# MCU.net
KiCad netlist of a schematic drawn in Altium Designer
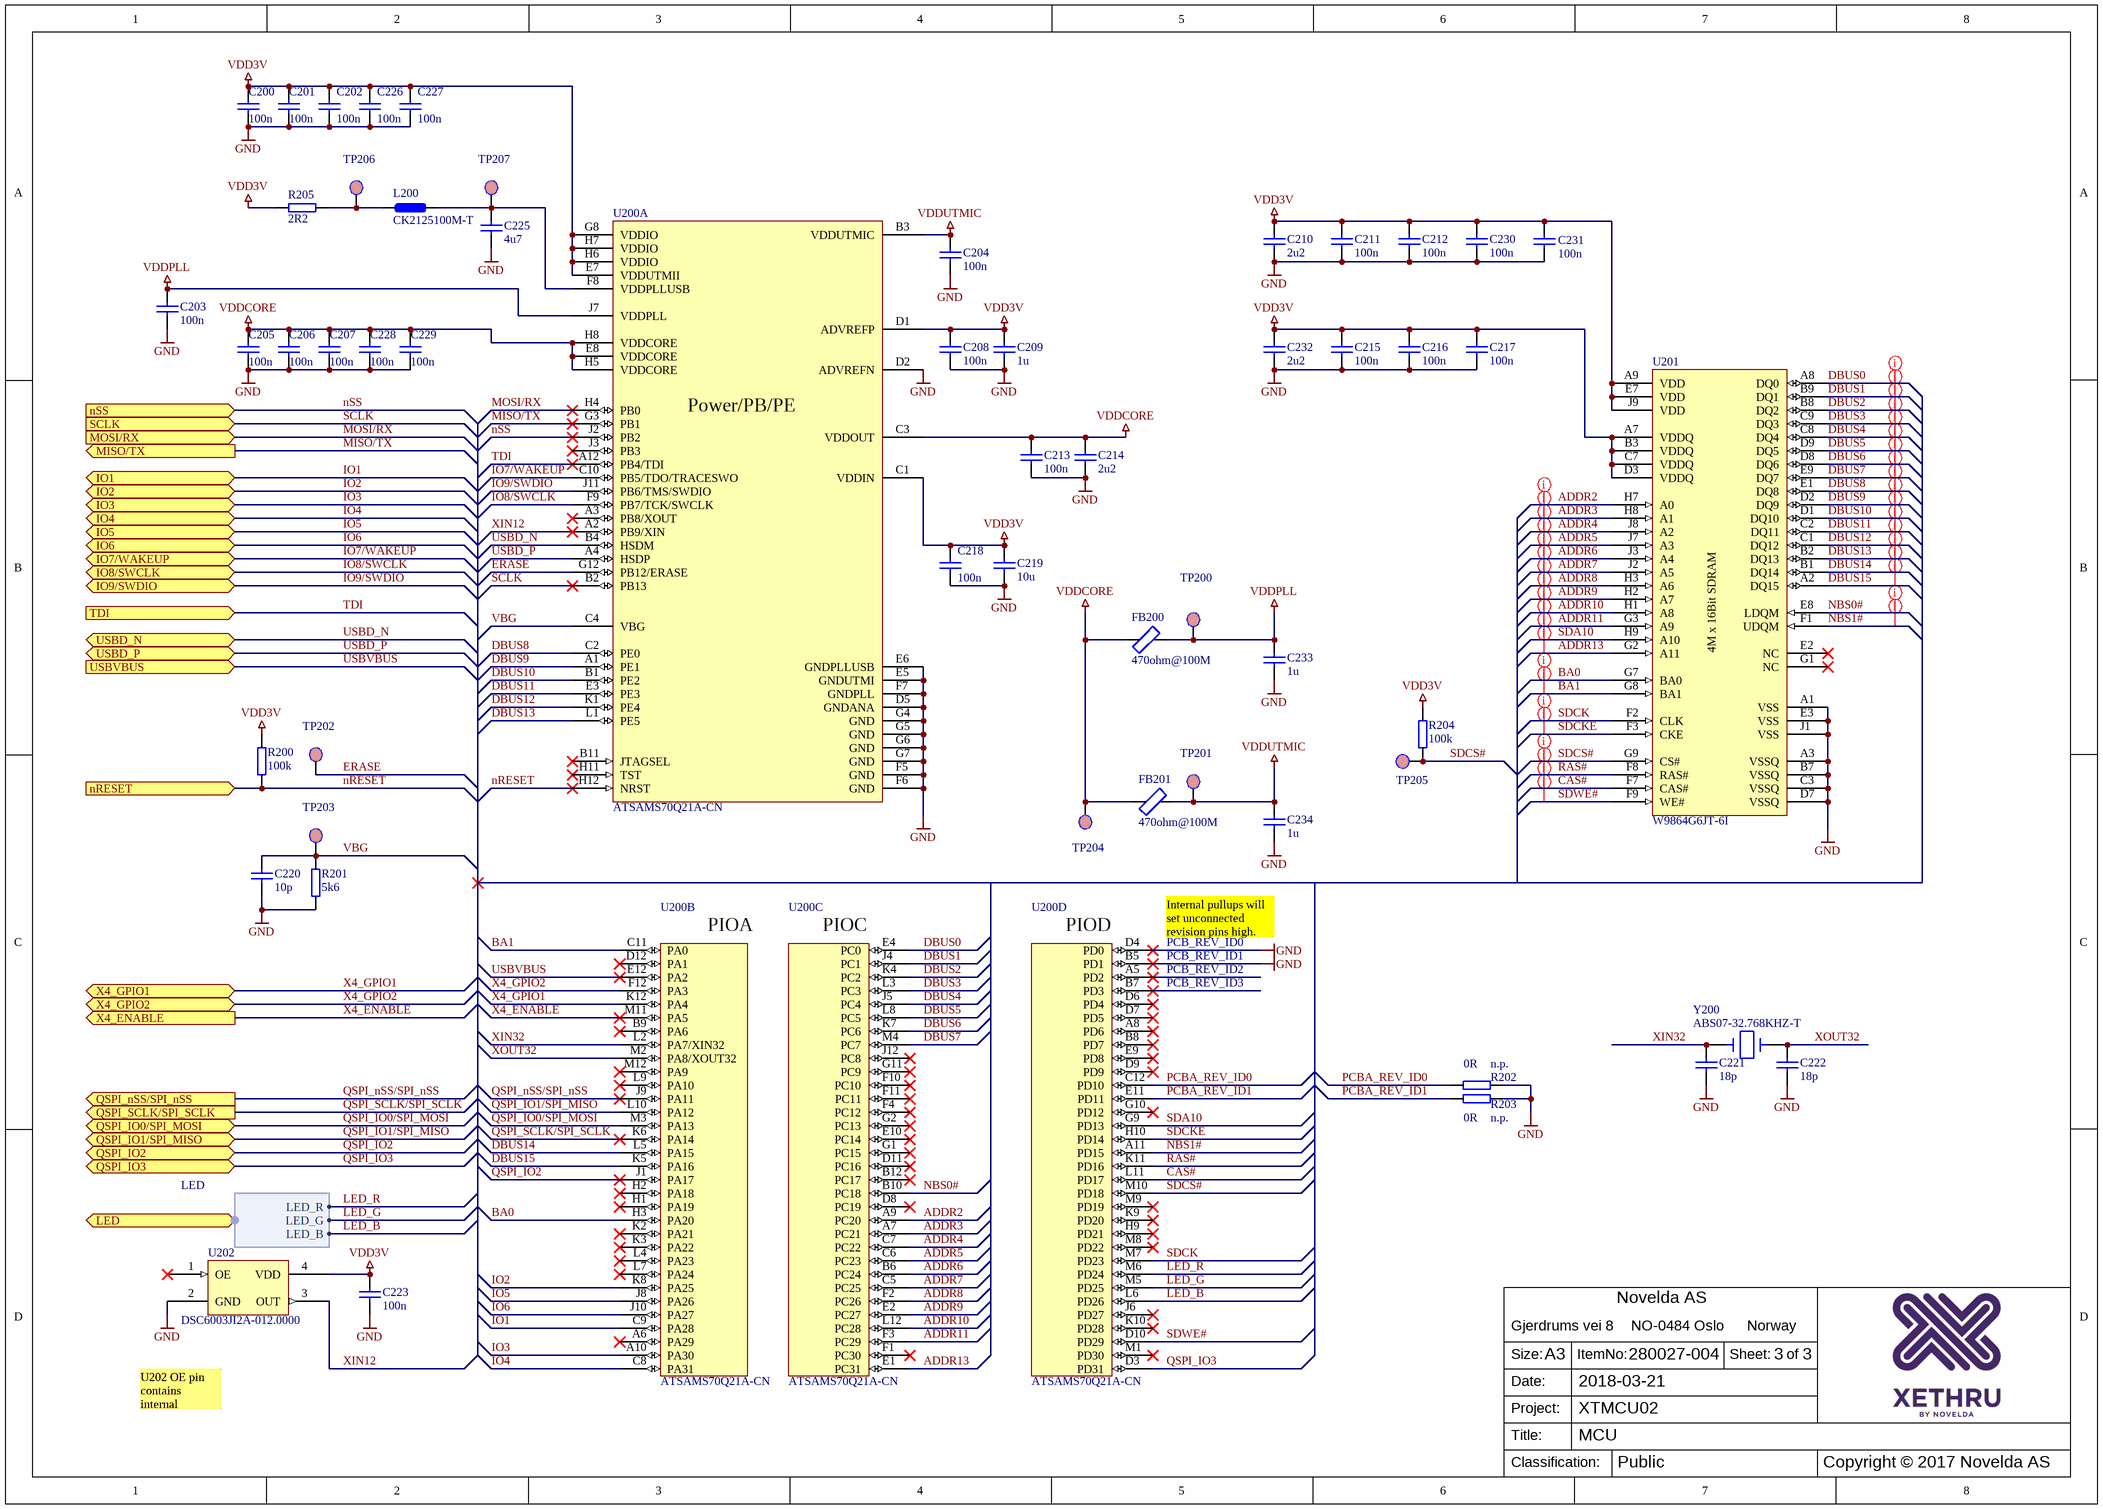
[diagram p0: MCU.SchDoc]

(export (version "E")
  (design (tool "Eeschema 10.0.6"))
  (components
    (comp (ref "C200")
      (value "100n")
      (footprint "0402-CAPACITOR-NONPOL")
      (description "CAPACITOR, 100n, 0402, 10%, 10V, X5R")
      (fields (field (name "MANUFACTURER") "--"))
      (libsource (lib "novelda_altiumlib") (part "CAPACITOR-NONPOL"))
    )
    (comp (ref "C201")
      (value "100n")
      (footprint "0402-CAPACITOR-NONPOL")
      (description "CAPACITOR, 100n, 0402, 10%, 10V, X5R")
      (fields (field (name "MANUFACTURER") "--"))
      (libsource (lib "novelda_altiumlib") (part "CAPACITOR-NONPOL"))
    )
    (comp (ref "C202")
      (value "100n")
      (footprint "0402-CAPACITOR-NONPOL")
      (description "CAPACITOR, 100n, 0402, 10%, 10V, X5R")
      (fields (field (name "MANUFACTURER") "--"))
      (libsource (lib "novelda_altiumlib") (part "CAPACITOR-NONPOL"))
    )
    (comp (ref "C203")
      (value "100n")
      (footprint "0402-CAPACITOR-NONPOL")
      (description "CAPACITOR, 100n, 0402, 10%, 10V, X5R")
      (fields (field (name "MANUFACTURER") "--"))
      (libsource (lib "novelda_altiumlib") (part "CAPACITOR-NONPOL"))
    )
    (comp (ref "C204")
      (value "100n")
      (footprint "0402-CAPACITOR-NONPOL")
      (description "CAPACITOR, 100n, 0402, 10%, 10V, X5R")
      (fields (field (name "MANUFACTURER") "--"))
      (libsource (lib "novelda_altiumlib") (part "CAPACITOR-NONPOL"))
    )
    (comp (ref "C205")
      (value "100n")
      (footprint "0402-CAPACITOR-NONPOL")
      (description "CAPACITOR, 100n, 0402, 10%, 10V, X5R")
      (fields (field (name "MANUFACTURER") "--"))
      (libsource (lib "novelda_altiumlib") (part "CAPACITOR-NONPOL"))
    )
    (comp (ref "C206")
      (value "100n")
      (footprint "0402-CAPACITOR-NONPOL")
      (description "CAPACITOR, 100n, 0402, 10%, 10V, X5R")
      (fields (field (name "MANUFACTURER") "--"))
      (libsource (lib "novelda_altiumlib") (part "CAPACITOR-NONPOL"))
    )
    (comp (ref "C207")
      (value "100n")
      (footprint "0402-CAPACITOR-NONPOL")
      (description "CAPACITOR, 100n, 0402, 10%, 10V, X5R")
      (fields (field (name "MANUFACTURER") "--"))
      (libsource (lib "novelda_altiumlib") (part "CAPACITOR-NONPOL"))
    )
    (comp (ref "C208")
      (value "100n")
      (footprint "0402-CAPACITOR-NONPOL")
      (description "CAPACITOR, 100n, 0402, 10%, 10V, X5R")
      (fields (field (name "MANUFACTURER") "--"))
      (libsource (lib "novelda_altiumlib") (part "CAPACITOR-NONPOL"))
    )
    (comp (ref "C209")
      (value "1u")
      (footprint "0402-CAPACITOR-NONPOL")
      (description "CAPACITOR, 1u, 0402, 10%, 10V, X5R")
      (fields (field (name "MANUFACTURER") "--"))
      (libsource (lib "novelda_altiumlib") (part "CAPACITOR-NONPOL"))
    )
    (comp (ref "C210")
      (value "2u2")
      (footprint "0402-CAPACITOR-NONPOL")
      (description "CAPACITOR, 2u2, 0402, 20%, 6V3, X5R")
      (fields (field (name "MANUFACTURER") "--"))
      (libsource (lib "novelda_altiumlib") (part "CAPACITOR-NONPOL"))
    )
    (comp (ref "C211")
      (value "100n")
      (footprint "0402-CAPACITOR-NONPOL")
      (description "CAPACITOR, 100n, 0402, 10%, 10V, X5R")
      (fields (field (name "MANUFACTURER") "--"))
      (libsource (lib "novelda_altiumlib") (part "CAPACITOR-NONPOL"))
    )
    (comp (ref "C212")
      (value "100n")
      (footprint "0402-CAPACITOR-NONPOL")
      (description "CAPACITOR, 100n, 0402, 10%, 10V, X5R")
      (fields (field (name "MANUFACTURER") "--"))
      (libsource (lib "novelda_altiumlib") (part "CAPACITOR-NONPOL"))
    )
    (comp (ref "C213")
      (value "100n")
      (footprint "0402-CAPACITOR-NONPOL")
      (description "CAPACITOR, 100n, 0402, 10%, 10V, X5R")
      (fields (field (name "MANUFACTURER") "--"))
      (libsource (lib "novelda_altiumlib") (part "CAPACITOR-NONPOL"))
    )
    (comp (ref "C214")
      (value "2u2")
      (footprint "0402-CAPACITOR-NONPOL")
      (description "CAPACITOR, 2u2, 0402, 20%, 6V3, X5R")
      (fields (field (name "MANUFACTURER") "--"))
      (libsource (lib "novelda_altiumlib") (part "CAPACITOR-NONPOL"))
    )
    (comp (ref "C215")
      (value "100n")
      (footprint "0402-CAPACITOR-NONPOL")
      (description "CAPACITOR, 100n, 0402, 10%, 10V, X5R")
      (fields (field (name "MANUFACTURER") "--"))
      (libsource (lib "novelda_altiumlib") (part "CAPACITOR-NONPOL"))
    )
    (comp (ref "C216")
      (value "100n")
      (footprint "0402-CAPACITOR-NONPOL")
      (description "CAPACITOR, 100n, 0402, 10%, 10V, X5R")
      (fields (field (name "MANUFACTURER") "--"))
      (libsource (lib "novelda_altiumlib") (part "CAPACITOR-NONPOL"))
    )
    (comp (ref "C217")
      (value "100n")
      (footprint "0402-CAPACITOR-NONPOL")
      (description "CAPACITOR, 100n, 0402, 10%, 10V, X5R")
      (fields (field (name "MANUFACTURER") "--"))
      (libsource (lib "novelda_altiumlib") (part "CAPACITOR-NONPOL"))
    )
    (comp (ref "C218")
      (value "100n")
      (footprint "0402-CAPACITOR-NONPOL")
      (description "CAPACITOR, 100n, 0402, 10%, 10V, X5R")
      (fields (field (name "MANUFACTURER") "--"))
      (libsource (lib "novelda_altiumlib") (part "CAPACITOR-NONPOL"))
    )
    (comp (ref "C219")
      (value "10u")
      (footprint "0603-CAPACITOR-NONPOL")
      (description "CAPACITOR, 10u, 0603, 20%, 6V3, X5R")
      (fields (field (name "MANUFACTURER") "--"))
      (libsource (lib "novelda_altiumlib") (part "CAPACITOR-NONPOL"))
    )
    (comp (ref "C220")
      (value "10p")
      (footprint "0402-CAPACITOR-NONPOL")
      (description "CAPACITOR, 10p, 0402, 5%, 50V, NP0")
      (fields (field (name "MANUFACTURER") "--"))
      (libsource (lib "novelda_altiumlib") (part "CAPACITOR-NONPOL"))
    )
    (comp (ref "C221")
      (value "18p")
      (footprint "0402-CAPACITOR-NONPOL")
      (description "CAPACITOR, 18p, 0402, 5%, 50V, NP0")
      (fields (field (name "MANUFACTURER") "--"))
      (libsource (lib "novelda_altiumlib") (part "CAPACITOR-NONPOL"))
    )
    (comp (ref "C222")
      (value "18p")
      (footprint "0402-CAPACITOR-NONPOL")
      (description "CAPACITOR, 18p, 0402, 5%, 50V, NP0")
      (fields (field (name "MANUFACTURER") "--"))
      (libsource (lib "novelda_altiumlib") (part "CAPACITOR-NONPOL"))
    )
    (comp (ref "C223")
      (value "100n")
      (footprint "0402-CAPACITOR-NONPOL")
      (description "CAPACITOR, 100n, 0402, 10%, 10V, X5R")
      (fields (field (name "MANUFACTURER") "--"))
      (libsource (lib "novelda_altiumlib") (part "CAPACITOR-NONPOL"))
    )
    (comp (ref "C225")
      (value "4u7")
      (footprint "0603-CAPACITOR-NONPOL")
      (description "CAPACITOR, 4u7, 0603, 10%, 10V, X5R")
      (fields (field (name "MANUFACTURER") "--"))
      (libsource (lib "novelda_altiumlib") (part "CAPACITOR-NONPOL"))
    )
    (comp (ref "C226")
      (value "100n")
      (footprint "0402-CAPACITOR-NONPOL")
      (description "CAPACITOR, 100n, 0402, 10%, 10V, X5R")
      (fields (field (name "MANUFACTURER") "--"))
      (libsource (lib "novelda_altiumlib") (part "CAPACITOR-NONPOL"))
    )
    (comp (ref "C227")
      (value "100n")
      (footprint "0402-CAPACITOR-NONPOL")
      (description "CAPACITOR, 100n, 0402, 10%, 10V, X5R")
      (fields (field (name "MANUFACTURER") "--"))
      (libsource (lib "novelda_altiumlib") (part "CAPACITOR-NONPOL"))
    )
    (comp (ref "C228")
      (value "100n")
      (footprint "0402-CAPACITOR-NONPOL")
      (description "CAPACITOR, 100n, 0402, 10%, 10V, X5R")
      (fields (field (name "MANUFACTURER") "--"))
      (libsource (lib "novelda_altiumlib") (part "CAPACITOR-NONPOL"))
    )
    (comp (ref "C229")
      (value "100n")
      (footprint "0402-CAPACITOR-NONPOL")
      (description "CAPACITOR, 100n, 0402, 10%, 10V, X5R")
      (fields (field (name "MANUFACTURER") "--"))
      (libsource (lib "novelda_altiumlib") (part "CAPACITOR-NONPOL"))
    )
    (comp (ref "C230")
      (value "100n")
      (footprint "0402-CAPACITOR-NONPOL")
      (description "CAPACITOR, 100n, 0402, 10%, 10V, X5R")
      (fields (field (name "MANUFACTURER") "--"))
      (libsource (lib "novelda_altiumlib") (part "CAPACITOR-NONPOL"))
    )
    (comp (ref "C231")
      (value "100n")
      (footprint "0402-CAPACITOR-NONPOL")
      (description "CAPACITOR, 100n, 0402, 10%, 10V, X5R")
      (fields (field (name "MANUFACTURER") "--"))
      (libsource (lib "novelda_altiumlib") (part "CAPACITOR-NONPOL"))
    )
    (comp (ref "C232")
      (value "2u2")
      (footprint "0402-CAPACITOR-NONPOL")
      (description "CAPACITOR, 2u2, 0402, 20%, 6V3, X5R")
      (fields (field (name "MANUFACTURER") "--"))
      (libsource (lib "novelda_altiumlib") (part "CAPACITOR-NONPOL"))
    )
    (comp (ref "C233")
      (value "1u")
      (footprint "0402-CAPACITOR-NONPOL")
      (description "CAPACITOR, 1u, 0402, 10%, 10V, X5R")
      (fields (field (name "MANUFACTURER") "--"))
      (libsource (lib "novelda_altiumlib") (part "CAPACITOR-NONPOL"))
    )
    (comp (ref "C234")
      (value "1u")
      (footprint "0402-CAPACITOR-NONPOL")
      (description "CAPACITOR, 1u, 0402, 10%, 10V, X5R")
      (fields (field (name "MANUFACTURER") "--"))
      (libsource (lib "novelda_altiumlib") (part "CAPACITOR-NONPOL"))
    )
    (comp (ref "FB200")
      (value "470ohm@100M")
      (footprint "200047")
      (description "FERRITE BEAD, 470ohm@100MHz, 1A")
      (fields (field (name "MANUFACTURER") "Murata") (field (name "MPN") "BLM18PG471SN1D"))
      (libsource (lib "novelda_altiumlib") (part "200047"))
    )
    (comp (ref "FB201")
      (value "470ohm@100M")
      (footprint "200047")
      (description "FERRITE BEAD, 470ohm@100MHz, 1A")
      (fields (field (name "MANUFACTURER") "Murata") (field (name "MPN") "BLM18PG471SN1D"))
      (libsource (lib "novelda_altiumlib") (part "200047"))
    )
    (comp (ref "L200")
      (value "CK2125100M-T")
      (footprint "200364")
      (description "INDUCTOR, 10u, 0805, 20%, 60mA, 650mOhm")
      (fields (field (name "MANUFACTURER") "TAIYO YUDEN"))
      (libsource (lib "novelda_altiumlib") (part "INDUCTOR"))
    )
    (comp (ref "R200")
      (value "100k")
      (footprint "0402-RESISTOR")
      (description "RESISTOR, 100k, 0402, 1%, 63mW")
      (fields (field (name "MANUFACTURER") "--"))
      (libsource (lib "novelda_altiumlib") (part "RESISTOR"))
    )
    (comp (ref "R201")
      (value "5k6")
      (footprint "0402-RESISTOR")
      (description "RESISTOR, 5k6, 0402, 1%, 63mW")
      (fields (field (name "MANUFACTURER") "--"))
      (libsource (lib "novelda_altiumlib") (part "RESISTOR"))
    )
    (comp (ref "R202")
      (value "0R")
      (footprint "0402-RESISTOR")
      (description "RESISTOR, 0R, 0402, 5%, 63mW")
      (fields (field (name "MANUFACTURER") "--") (field (name "NOTES") "n.p."))
      (libsource (lib "novelda_altiumlib") (part "RESISTOR"))
    )
    (comp (ref "R203")
      (value "0R")
      (footprint "0402-RESISTOR")
      (description "RESISTOR, 0R, 0402, 5%, 63mW")
      (fields (field (name "MANUFACTURER") "--") (field (name "NOTES") "n.p."))
      (libsource (lib "novelda_altiumlib") (part "RESISTOR"))
    )
    (comp (ref "R204")
      (value "100k")
      (footprint "0402-RESISTOR")
      (description "RESISTOR, 100k, 0402, 1%, 63mW")
      (fields (field (name "MANUFACTURER") "--"))
      (libsource (lib "novelda_altiumlib") (part "RESISTOR"))
    )
    (comp (ref "R205")
      (value "2R2")
      (footprint "0402-RESISTOR")
      (description "RESISTOR, 2R2, 0402, 1%, 63mW")
      (fields (field (name "MANUFACTURER") "--"))
      (libsource (lib "novelda_altiumlib") (part "RESISTOR"))
    )
    (comp (ref "TP200")
      (value "TP-MDA")
      (footprint "ALTIUM-0001")
      (description "TESTPOINT FOR MDA-TEST, 1mm ROUND, SMD")
      (libsource (lib "novelda_altiumlib") (part "TESTPOINT-MDA"))
    )
    (comp (ref "TP201")
      (value "TP-MDA")
      (footprint "ALTIUM-0001")
      (description "TESTPOINT FOR MDA-TEST, 1mm ROUND, SMD")
      (libsource (lib "novelda_altiumlib") (part "TESTPOINT-MDA"))
    )
    (comp (ref "TP202")
      (value "TP-MDA")
      (footprint "ALTIUM-0001")
      (description "TESTPOINT FOR MDA-TEST, 1mm ROUND, SMD")
      (libsource (lib "novelda_altiumlib") (part "TESTPOINT-MDA"))
    )
    (comp (ref "TP203")
      (value "TP-MDA")
      (footprint "ALTIUM-0001")
      (description "TESTPOINT FOR MDA-TEST, 1mm ROUND, SMD")
      (libsource (lib "novelda_altiumlib") (part "TESTPOINT-MDA"))
    )
    (comp (ref "TP204")
      (value "TP-MDA")
      (footprint "ALTIUM-0001")
      (description "TESTPOINT FOR MDA-TEST, 1mm ROUND, SMD")
      (libsource (lib "novelda_altiumlib") (part "TESTPOINT-MDA"))
    )
    (comp (ref "TP205")
      (value "TP-MDA")
      (footprint "ALTIUM-0001")
      (description "TESTPOINT FOR MDA-TEST, 1mm ROUND, SMD")
      (libsource (lib "novelda_altiumlib") (part "TESTPOINT-MDA"))
    )
    (comp (ref "TP206")
      (value "TP-MDA")
      (footprint "ALTIUM-0001")
      (description "TESTPOINT FOR MDA-TEST, 1mm ROUND, SMD")
      (libsource (lib "novelda_altiumlib") (part "TESTPOINT-MDA"))
    )
    (comp (ref "TP207")
      (value "TP-MDA")
      (footprint "ALTIUM-0001")
      (description "TESTPOINT FOR MDA-TEST, 1mm ROUND, SMD")
      (libsource (lib "novelda_altiumlib") (part "TESTPOINT-MDA"))
    )
    (comp (ref "U200")
      (value "ATSAMS70Q21A-CN")
      (footprint "200353")
      (description "ATSAMS70Q21A-CN, MCU, LFBGA144, 2048k Flash, 384k SRAM")
      (fields (field (name "MANUFACTURER") "Atmel"))
      (libsource (lib "novelda_altiumlib") (part "200353"))
    )
    (comp (ref "U201")
      (value "W9864G6JT-6I")
      (footprint "200282")
      (description "IC, SYNCHRONOUS DRAM (SDRAM), 64MBIT, 6NS, 166MHZ, 4M x 16BIT, 54FBGA")
      (fields (field (name "MANUFACTURER") "Winbond Electronics Corp."))
      (libsource (lib "novelda_altiumlib") (part "200282"))
    )
    (comp (ref "U202")
      (value "DSC6003JI2A-012.0000")
      (footprint "200365")
      (description "DSC6003JI2A-012.0000, 12MHZ CMOS MEMS OSCILLATOR 2.5X2MM")
      (fields (field (name "MANUFACTURER") "Microchip Technology"))
      (libsource (lib "novelda_altiumlib") (part "200365"))
    )
    (comp (ref "Y200")
      (value "ABS07-32.768KHZ-T")
      (footprint "200042")
      (description "CRYSTAL, 32.768KHZ, 12.5PF, SMD")
      (fields (field (name "MANUFACTURER") "Abracon"))
      (libsource (lib "novelda_altiumlib") (part "200042"))
    )
  )
  (nets
    (net (code "2") (name "/ADDR2") (class "Default")
      (node (ref "U200") (pin "A9") (pinfunction "PC20_A9") (pintype "bidirectional"))
      (node (ref "U201") (pin "H7") (pinfunction "A0_H7") (pintype "input"))
    )
    (net (code "3") (name "/ADDR3") (class "Default")
      (node (ref "U200") (pin "A7") (pinfunction "PC21_A7") (pintype "bidirectional"))
      (node (ref "U201") (pin "H8") (pinfunction "A1_H8") (pintype "input"))
    )
    (net (code "4") (name "/ADDR4") (class "Default")
      (node (ref "U200") (pin "C7") (pinfunction "PC22_C7") (pintype "bidirectional"))
      (node (ref "U201") (pin "J8") (pinfunction "A2_J8") (pintype "input"))
    )
    (net (code "5") (name "/ADDR5") (class "Default")
      (node (ref "U200") (pin "C6") (pinfunction "PC23_C6") (pintype "bidirectional"))
      (node (ref "U201") (pin "J7") (pinfunction "A3_J7") (pintype "input"))
    )
    (net (code "6") (name "/ADDR6") (class "Default")
      (node (ref "U200") (pin "B6") (pinfunction "PC24_B6") (pintype "bidirectional"))
      (node (ref "U201") (pin "J3") (pinfunction "A4_J3") (pintype "input"))
    )
    (net (code "7") (name "/ADDR7") (class "Default")
      (node (ref "U200") (pin "C5") (pinfunction "PC25_C5") (pintype "bidirectional"))
      (node (ref "U201") (pin "J2") (pinfunction "A5_J2") (pintype "input"))
    )
    (net (code "8") (name "/ADDR8") (class "Default")
      (node (ref "U200") (pin "F2") (pinfunction "PC26_F2") (pintype "bidirectional"))
      (node (ref "U201") (pin "H3") (pinfunction "A6_H3") (pintype "input"))
    )
    (net (code "9") (name "/ADDR9") (class "Default")
      (node (ref "U200") (pin "E2") (pinfunction "PC27_E2") (pintype "bidirectional"))
      (node (ref "U201") (pin "H2") (pinfunction "A7_H2") (pintype "input"))
    )
    (net (code "10") (name "/ADDR10") (class "Default")
      (node (ref "U200") (pin "L12") (pinfunction "PC28_L12") (pintype "bidirectional"))
      (node (ref "U201") (pin "H1") (pinfunction "A8_H1") (pintype "input"))
    )
    (net (code "11") (name "/ADDR11") (class "Default")
      (node (ref "U200") (pin "F3") (pinfunction "PC29_F3") (pintype "bidirectional"))
      (node (ref "U201") (pin "G3") (pinfunction "A9_G3") (pintype "input"))
    )
    (net (code "12") (name "/ADDR13") (class "Default")
      (node (ref "U200") (pin "E1") (pinfunction "PC31_E1") (pintype "bidirectional"))
      (node (ref "U201") (pin "G2") (pinfunction "A11_G2") (pintype "input"))
    )
    (net (code "13") (name "/BA0") (class "Default")
      (node (ref "U200") (pin "H3") (pinfunction "PA20_H3") (pintype "bidirectional"))
      (node (ref "U201") (pin "G7") (pinfunction "BA0_G7") (pintype "input"))
    )
    (net (code "14") (name "/BA1") (class "Default")
      (node (ref "U200") (pin "C11") (pinfunction "PA0_C11") (pintype "bidirectional"))
      (node (ref "U201") (pin "G8") (pinfunction "BA1_G8") (pintype "input"))
    )
    (net (code "15") (name "/CAS#") (class "Default")
      (node (ref "U200") (pin "L11") (pinfunction "PD17_L11") (pintype "bidirectional"))
      (node (ref "U201") (pin "F7") (pinfunction "CAS#_F7") (pintype "input"))
    )
    (net (code "16") (name "/DBUS0") (class "Default")
      (node (ref "U200") (pin "E4") (pinfunction "PC0_E4") (pintype "bidirectional"))
      (node (ref "U201") (pin "A8") (pinfunction "DQ0_A8") (pintype "bidirectional"))
    )
    (net (code "17") (name "/DBUS1") (class "Default")
      (node (ref "U200") (pin "J4") (pinfunction "PC1_J4") (pintype "bidirectional"))
      (node (ref "U201") (pin "B9") (pinfunction "DQ1_B9") (pintype "bidirectional"))
    )
    (net (code "18") (name "/DBUS2") (class "Default")
      (node (ref "U200") (pin "K4") (pinfunction "PC2_K4") (pintype "bidirectional"))
      (node (ref "U201") (pin "B8") (pinfunction "DQ2_B8") (pintype "bidirectional"))
    )
    (net (code "19") (name "/DBUS3") (class "Default")
      (node (ref "U200") (pin "L3") (pinfunction "PC3_L3") (pintype "bidirectional"))
      (node (ref "U201") (pin "C9") (pinfunction "DQ3_C9") (pintype "bidirectional"))
    )
    (net (code "20") (name "/DBUS4") (class "Default")
      (node (ref "U200") (pin "J5") (pinfunction "PC4_J5") (pintype "bidirectional"))
      (node (ref "U201") (pin "C8") (pinfunction "DQ4_C8") (pintype "bidirectional"))
    )
    (net (code "21") (name "/DBUS5") (class "Default")
      (node (ref "U200") (pin "L8") (pinfunction "PC5_L8") (pintype "bidirectional"))
      (node (ref "U201") (pin "D9") (pinfunction "DQ5_D9") (pintype "bidirectional"))
    )
    (net (code "22") (name "/DBUS6") (class "Default")
      (node (ref "U200") (pin "K7") (pinfunction "PC6_K7") (pintype "bidirectional"))
      (node (ref "U201") (pin "D8") (pinfunction "DQ6_D8") (pintype "bidirectional"))
    )
    (net (code "23") (name "/DBUS7") (class "Default")
      (node (ref "U200") (pin "M4") (pinfunction "PC7_M4") (pintype "bidirectional"))
      (node (ref "U201") (pin "E9") (pinfunction "DQ7_E9") (pintype "bidirectional"))
    )
    (net (code "24") (name "/DBUS8") (class "Default")
      (node (ref "U200") (pin "C2") (pinfunction "PE0_C2") (pintype "bidirectional"))
      (node (ref "U201") (pin "E1") (pinfunction "DQ8_E1") (pintype "bidirectional"))
    )
    (net (code "25") (name "/DBUS9") (class "Default")
      (node (ref "U200") (pin "A1") (pinfunction "PE1_A1") (pintype "bidirectional"))
      (node (ref "U201") (pin "D2") (pinfunction "DQ9_D2") (pintype "bidirectional"))
    )
    (net (code "26") (name "/DBUS10") (class "Default")
      (node (ref "U200") (pin "B1") (pinfunction "PE2_B1") (pintype "bidirectional"))
      (node (ref "U201") (pin "D1") (pinfunction "DQ10_D1") (pintype "bidirectional"))
    )
    (net (code "27") (name "/DBUS11") (class "Default")
      (node (ref "U200") (pin "E3") (pinfunction "PE3_E3") (pintype "bidirectional"))
      (node (ref "U201") (pin "C2") (pinfunction "DQ11_C2") (pintype "bidirectional"))
    )
    (net (code "28") (name "/DBUS12") (class "Default")
      (node (ref "U200") (pin "K1") (pinfunction "PE4_K1") (pintype "bidirectional"))
      (node (ref "U201") (pin "C1") (pinfunction "DQ12_C1") (pintype "bidirectional"))
    )
    (net (code "29") (name "/DBUS13") (class "Default")
      (node (ref "U200") (pin "L1") (pinfunction "PE5_L1") (pintype "bidirectional"))
      (node (ref "U201") (pin "B2") (pinfunction "DQ13_B2") (pintype "bidirectional"))
    )
    (net (code "30") (name "/DBUS14") (class "Default")
      (node (ref "U200") (pin "L5") (pinfunction "PA15_L5") (pintype "bidirectional"))
      (node (ref "U201") (pin "B1") (pinfunction "DQ14_B1") (pintype "bidirectional"))
    )
    (net (code "31") (name "/DBUS15") (class "Default")
      (node (ref "U200") (pin "K5") (pinfunction "PA16_K5") (pintype "bidirectional"))
      (node (ref "U201") (pin "A2") (pinfunction "DQ15_A2") (pintype "bidirectional"))
    )
    (net (code "32") (name "/ERASE") (class "Default")
      (node (ref "TP202") (pin "1") (pintype "passive"))
      (node (ref "U200") (pin "G12") (pinfunction "PB12/ERASE_G12") (pintype "bidirectional"))
    )
    (net (code "33") (name "/IO1") (class "Default")
      (node (ref "U200") (pin "C9") (pinfunction "PA28_C9") (pintype "bidirectional"))
    )
    (net (code "34") (name "/IO2") (class "Default")
      (node (ref "U200") (pin "K8") (pinfunction "PA25_K8") (pintype "bidirectional"))
    )
    (net (code "35") (name "/IO3") (class "Default")
      (node (ref "U200") (pin "A10") (pinfunction "PA30_A10") (pintype "bidirectional"))
    )
    (net (code "36") (name "/IO4") (class "Default")
      (node (ref "U200") (pin "C8") (pinfunction "PA31_C8") (pintype "bidirectional"))
    )
    (net (code "37") (name "/IO5") (class "Default")
      (node (ref "U200") (pin "J8") (pinfunction "PA26_J8") (pintype "bidirectional"))
    )
    (net (code "38") (name "/IO6") (class "Default")
      (node (ref "U200") (pin "J10") (pinfunction "PA27_J10") (pintype "bidirectional"))
    )
    (net (code "39") (name "/IO7{slash}WAKEUP") (class "Default")
      (node (ref "U200") (pin "C10") (pinfunction "PB5/TDO/TRACESWO_C10") (pintype "bidirectional"))
    )
    (net (code "40") (name "/IO8{slash}SWCLK") (class "Default")
      (node (ref "U200") (pin "F9") (pinfunction "PB7/TCK/SWCLK_F9") (pintype "bidirectional"))
    )
    (net (code "41") (name "/IO9{slash}SWDIO") (class "Default")
      (node (ref "U200") (pin "J11") (pinfunction "PB6/TMS/SWDIO_J11") (pintype "bidirectional"))
    )
    (net (code "42") (name "/LED_B") (class "Default")
      (node (ref "U200") (pin "L6") (pinfunction "PD26_L6") (pintype "bidirectional"))
    )
    (net (code "43") (name "/LED_G") (class "Default")
      (node (ref "U200") (pin "M5") (pinfunction "PD25_M5") (pintype "bidirectional"))
    )
    (net (code "44") (name "/LED_R") (class "Default")
      (node (ref "U200") (pin "M6") (pinfunction "PD24_M6") (pintype "bidirectional"))
    )
    (net (code "45") (name "/MISO{slash}TX") (class "Default")
      (node (ref "U200") (pin "G3") (pinfunction "PB1_G3") (pintype "bidirectional+no_connect"))
    )
    (net (code "46") (name "/MOSI{slash}RX") (class "Default")
      (node (ref "U200") (pin "H4") (pinfunction "PB0_H4") (pintype "bidirectional+no_connect"))
    )
    (net (code "47") (name "/NBS0#") (class "Default")
      (node (ref "U200") (pin "B10") (pinfunction "PC18_B10") (pintype "bidirectional"))
      (node (ref "U201") (pin "E8") (pinfunction "LDQM_E8") (pintype "input"))
    )
    (net (code "48") (name "/NBS1#") (class "Default")
      (node (ref "U200") (pin "A11") (pinfunction "PD15_A11") (pintype "bidirectional"))
      (node (ref "U201") (pin "F1") (pinfunction "UDQM_F1") (pintype "input"))
    )
    (net (code "49") (name "/PCBA_REV_ID0") (class "Default")
      (node (ref "R202") (pin "1") (pinfunction "1_1") (pintype "passive"))
      (node (ref "U200") (pin "C12") (pinfunction "PD10_C12") (pintype "bidirectional"))
    )
    (net (code "50") (name "/PCBA_REV_ID1") (class "Default")
      (node (ref "R203") (pin "1") (pinfunction "1_1") (pintype "passive"))
      (node (ref "U200") (pin "E11") (pinfunction "PD11_E11") (pintype "bidirectional"))
    )
    (net (code "51") (name "/QSPI_IO0{slash}SPI_MOSI") (class "Default")
      (node (ref "U200") (pin "M3") (pinfunction "PA13_M3") (pintype "bidirectional"))
    )
    (net (code "52") (name "/QSPI_IO1{slash}SPI_MISO") (class "Default")
      (node (ref "U200") (pin "L10") (pinfunction "PA12_L10") (pintype "bidirectional"))
    )
    (net (code "53") (name "/QSPI_IO2") (class "Default")
      (node (ref "U200") (pin "J1") (pinfunction "PA17_J1") (pintype "bidirectional"))
    )
    (net (code "54") (name "/QSPI_IO3") (class "Default")
      (node (ref "U200") (pin "D3") (pinfunction "PD31_D3") (pintype "bidirectional"))
    )
    (net (code "55") (name "/QSPI_SCLK{slash}SPI_SCLK") (class "Default")
      (node (ref "U200") (pin "K6") (pinfunction "PA14_K6") (pintype "bidirectional+no_connect"))
    )
    (net (code "56") (name "/QSPI_nSS{slash}SPI_nSS") (class "Default")
      (node (ref "U200") (pin "J9") (pinfunction "PA11_J9") (pintype "bidirectional+no_connect"))
    )
    (net (code "57") (name "/RAS#") (class "Default")
      (node (ref "U200") (pin "K11") (pinfunction "PD16_K11") (pintype "bidirectional"))
      (node (ref "U201") (pin "F8") (pinfunction "RAS#_F8") (pintype "input"))
    )
    (net (code "58") (name "/SCLK") (class "Default")
      (node (ref "U200") (pin "B2") (pinfunction "PB13_B2") (pintype "bidirectional"))
    )
    (net (code "59") (name "/SDA10") (class "Default")
      (node (ref "U200") (pin "G9") (pinfunction "PD13_G9") (pintype "bidirectional"))
      (node (ref "U201") (pin "H9") (pinfunction "A10_H9") (pintype "input"))
    )
    (net (code "60") (name "/SDCK") (class "Default")
      (node (ref "U200") (pin "M7") (pinfunction "PD23_M7") (pintype "bidirectional"))
      (node (ref "U201") (pin "F2") (pinfunction "CLK_F2") (pintype "input"))
    )
    (net (code "61") (name "/SDCKE") (class "Default")
      (node (ref "U200") (pin "H10") (pinfunction "PD14_H10") (pintype "bidirectional"))
      (node (ref "U201") (pin "F3") (pinfunction "CKE_F3") (pintype "input"))
    )
    (net (code "62") (name "/SDCS#") (class "Default")
      (node (ref "R204") (pin "1") (pinfunction "1_1") (pintype "passive"))
      (node (ref "TP205") (pin "1") (pintype "passive"))
      (node (ref "U200") (pin "M10") (pinfunction "PD18_M10") (pintype "bidirectional"))
      (node (ref "U201") (pin "G9") (pinfunction "CS#_G9") (pintype "input"))
    )
    (net (code "63") (name "/SDWE#") (class "Default")
      (node (ref "U200") (pin "D10") (pinfunction "PD29_D10") (pintype "bidirectional"))
      (node (ref "U201") (pin "F9") (pinfunction "WE#_F9") (pintype "input"))
    )
    (net (code "64") (name "/TDI") (class "Default")
      (node (ref "U200") (pin "A12") (pinfunction "PB4/TDI_A12") (pintype "bidirectional+no_connect"))
    )
    (net (code "65") (name "/USBD_N") (class "Default")
      (node (ref "U200") (pin "B4") (pinfunction "HSDM_B4") (pintype "bidirectional"))
    )
    (net (code "66") (name "/USBD_P") (class "Default")
      (node (ref "U200") (pin "A4") (pinfunction "HSDP_A4") (pintype "bidirectional"))
    )
    (net (code "67") (name "/USBVBUS") (class "Default")
      (node (ref "U200") (pin "E12") (pinfunction "PA2_E12") (pintype "bidirectional+no_connect"))
    )
    (net (code "68") (name "/VBG") (class "Default")
      (node (ref "C220") (pin "1") (pinfunction "1_1") (pintype "passive"))
      (node (ref "R201") (pin "2") (pinfunction "2_2") (pintype "passive"))
      (node (ref "TP203") (pin "1") (pintype "passive"))
      (node (ref "U200") (pin "C4") (pinfunction "VBG_C4") (pintype "power_in"))
    )
    (net (code "69") (name "/X4_ENABLE") (class "Default")
      (node (ref "U200") (pin "M11") (pinfunction "PA5_M11") (pintype "bidirectional+no_connect"))
    )
    (net (code "70") (name "/X4_GPIO1") (class "Default")
      (node (ref "U200") (pin "K12") (pinfunction "PA4_K12") (pintype "bidirectional"))
    )
    (net (code "71") (name "/X4_GPIO2") (class "Default")
      (node (ref "U200") (pin "F12") (pinfunction "PA3_F12") (pintype "bidirectional"))
    )
    (net (code "72") (name "/XIN12") (class "Default")
      (node (ref "U200") (pin "A2") (pinfunction "PB9/XIN_A2") (pintype "bidirectional"))
      (node (ref "U202") (pin "3") (pinfunction "OUT_3") (pintype "output"))
    )
    (net (code "73") (name "/XIN32") (class "Default")
      (node (ref "C221") (pin "2") (pinfunction "2_2") (pintype "passive"))
      (node (ref "U200") (pin "L2") (pinfunction "PA7/XIN32_L2") (pintype "bidirectional"))
      (node (ref "Y200") (pin "1") (pinfunction "1_1") (pintype "passive"))
    )
    (net (code "74") (name "/XOUT32") (class "Default")
      (node (ref "C222") (pin "2") (pinfunction "2_2") (pintype "passive"))
      (node (ref "U200") (pin "M2") (pinfunction "PA8/XOUT32_M2") (pintype "bidirectional"))
      (node (ref "Y200") (pin "2") (pinfunction "2_2") (pintype "passive"))
    )
    (net (code "75") (name "/nRESET") (class "Default")
      (node (ref "R200") (pin "1") (pinfunction "1_1") (pintype "passive"))
      (node (ref "U200") (pin "H12") (pinfunction "NRST_H12") (pintype "input"))
    )
    (net (code "76") (name "/nSS") (class "Default")
      (node (ref "U200") (pin "J2") (pinfunction "PB2_J2") (pintype "bidirectional+no_connect"))
    )
    (net (code "78") (name "GND") (class "Default")
      (node (ref "C200") (pin "2") (pinfunction "2_2") (pintype "passive"))
      (node (ref "C201") (pin "1") (pinfunction "1_1") (pintype "passive"))
      (node (ref "C202") (pin "1") (pinfunction "1_1") (pintype "passive"))
      (node (ref "C203") (pin "1") (pinfunction "1_1") (pintype "passive"))
      (node (ref "C204") (pin "1") (pinfunction "1_1") (pintype "passive"))
      (node (ref "C205") (pin "2") (pinfunction "2_2") (pintype "passive"))
      (node (ref "C206") (pin "1") (pinfunction "1_1") (pintype "passive"))
      (node (ref "C207") (pin "1") (pinfunction "1_1") (pintype "passive"))
      (node (ref "C208") (pin "1") (pinfunction "1_1") (pintype "passive"))
      (node (ref "C209") (pin "1") (pinfunction "1_1") (pintype "passive"))
      (node (ref "C210") (pin "2") (pinfunction "2_2") (pintype "passive"))
      (node (ref "C211") (pin "1") (pinfunction "1_1") (pintype "passive"))
      (node (ref "C212") (pin "1") (pinfunction "1_1") (pintype "passive"))
      (node (ref "C213") (pin "1") (pinfunction "1_1") (pintype "passive"))
      (node (ref "C214") (pin "2") (pinfunction "2_2") (pintype "passive"))
      (node (ref "C215") (pin "1") (pinfunction "1_1") (pintype "passive"))
      (node (ref "C216") (pin "1") (pinfunction "1_1") (pintype "passive"))
      (node (ref "C217") (pin "1") (pinfunction "1_1") (pintype "passive"))
      (node (ref "C218") (pin "1") (pinfunction "1_1") (pintype "passive"))
      (node (ref "C219") (pin "1") (pinfunction "1_1") (pintype "passive"))
      (node (ref "C220") (pin "2") (pinfunction "2_2") (pintype "passive"))
      (node (ref "C221") (pin "1") (pinfunction "1_1") (pintype "passive"))
      (node (ref "C222") (pin "1") (pinfunction "1_1") (pintype "passive"))
      (node (ref "C223") (pin "2") (pinfunction "2_2") (pintype "passive"))
      (node (ref "C225") (pin "1") (pinfunction "1_1") (pintype "passive"))
      (node (ref "C226") (pin "1") (pinfunction "1_1") (pintype "passive"))
      (node (ref "C227") (pin "1") (pinfunction "1_1") (pintype "passive"))
      (node (ref "C228") (pin "1") (pinfunction "1_1") (pintype "passive"))
      (node (ref "C229") (pin "1") (pinfunction "1_1") (pintype "passive"))
      (node (ref "C230") (pin "1") (pinfunction "1_1") (pintype "passive"))
      (node (ref "C231") (pin "1") (pinfunction "1_1") (pintype "passive"))
      (node (ref "C232") (pin "2") (pinfunction "2_2") (pintype "passive"))
      (node (ref "C233") (pin "1") (pinfunction "1_1") (pintype "passive"))
      (node (ref "C234") (pin "1") (pinfunction "1_1") (pintype "passive"))
      (node (ref "R201") (pin "1") (pinfunction "1_1") (pintype "passive"))
      (node (ref "R202") (pin "2") (pinfunction "2_2") (pintype "passive"))
      (node (ref "R203") (pin "2") (pinfunction "2_2") (pintype "passive"))
      (node (ref "U200") (pin "B5") (pinfunction "PD1_B5") (pintype "bidirectional"))
      (node (ref "U200") (pin "D2") (pinfunction "ADVREFN_D2") (pintype "passive"))
      (node (ref "U200") (pin "D4") (pinfunction "PD0_D4") (pintype "bidirectional"))
      (node (ref "U200") (pin "D5") (pinfunction "GNDANA_D5") (pintype "power_in"))
      (node (ref "U200") (pin "E5") (pinfunction "GNDUTMI_E5") (pintype "power_in"))
      (node (ref "U200") (pin "E6") (pinfunction "GNDPLLUSB_E6") (pintype "power_in"))
      (node (ref "U200") (pin "F5") (pinfunction "GND_F5") (pintype "power_in"))
      (node (ref "U200") (pin "F6") (pinfunction "GND_F6") (pintype "power_in"))
      (node (ref "U200") (pin "F7") (pinfunction "GNDPLL_F7") (pintype "power_in"))
      (node (ref "U200") (pin "G4") (pinfunction "GND_G4") (pintype "power_in"))
      (node (ref "U200") (pin "G5") (pinfunction "GND_G5") (pintype "power_in"))
      (node (ref "U200") (pin "G6") (pinfunction "GND_G6") (pintype "power_in"))
      (node (ref "U200") (pin "G7") (pinfunction "GND_G7") (pintype "power_in"))
      (node (ref "U201") (pin "A1") (pinfunction "VSS_A1") (pintype "power_in"))
      (node (ref "U201") (pin "A3") (pinfunction "VSSQ_A3") (pintype "power_in"))
      (node (ref "U201") (pin "B7") (pinfunction "VSSQ_B7") (pintype "power_in"))
      (node (ref "U201") (pin "C3") (pinfunction "VSSQ_C3") (pintype "power_in"))
      (node (ref "U201") (pin "D7") (pinfunction "VSSQ_D7") (pintype "power_in"))
      (node (ref "U201") (pin "E3") (pinfunction "VSS_E3") (pintype "power_in"))
      (node (ref "U201") (pin "J1") (pinfunction "VSS_J1") (pintype "power_in"))
      (node (ref "U202") (pin "2") (pinfunction "GND_2") (pintype "power_in"))
    )
    (net (code "79") (name "Net-(L200-Pad1)") (class "Default")
      (node (ref "L200") (pin "1") (pinfunction "1_1") (pintype "passive"))
      (node (ref "R205") (pin "2") (pinfunction "2_2") (pintype "passive"))
      (node (ref "TP206") (pin "1") (pintype "passive"))
    )
    (net (code "80") (name "Net-(U200A-VDDPLLUSB)") (class "Default")
      (node (ref "C225") (pin "2") (pinfunction "2_2") (pintype "passive"))
      (node (ref "L200") (pin "2") (pinfunction "2_2") (pintype "passive"))
      (node (ref "TP207") (pin "1") (pintype "passive"))
      (node (ref "U200") (pin "F8") (pinfunction "VDDPLLUSB_F8") (pintype "power_in"))
    )
    (net (code "81") (name "VDD3V") (class "Default")
      (node (ref "C200") (pin "1") (pinfunction "1_1") (pintype "passive"))
      (node (ref "C201") (pin "2") (pinfunction "2_2") (pintype "passive"))
      (node (ref "C202") (pin "2") (pinfunction "2_2") (pintype "passive"))
      (node (ref "C208") (pin "2") (pinfunction "2_2") (pintype "passive"))
      (node (ref "C209") (pin "2") (pinfunction "2_2") (pintype "passive"))
      (node (ref "C210") (pin "1") (pinfunction "1_1") (pintype "passive"))
      (node (ref "C211") (pin "2") (pinfunction "2_2") (pintype "passive"))
      (node (ref "C212") (pin "2") (pinfunction "2_2") (pintype "passive"))
      (node (ref "C215") (pin "2") (pinfunction "2_2") (pintype "passive"))
      (node (ref "C216") (pin "2") (pinfunction "2_2") (pintype "passive"))
      (node (ref "C217") (pin "2") (pinfunction "2_2") (pintype "passive"))
      (node (ref "C218") (pin "2") (pinfunction "2_2") (pintype "passive"))
      (node (ref "C219") (pin "2") (pinfunction "2_2") (pintype "passive"))
      (node (ref "C223") (pin "1") (pinfunction "1_1") (pintype "passive"))
      (node (ref "C226") (pin "2") (pinfunction "2_2") (pintype "passive"))
      (node (ref "C227") (pin "2") (pinfunction "2_2") (pintype "passive"))
      (node (ref "C230") (pin "2") (pinfunction "2_2") (pintype "passive"))
      (node (ref "C231") (pin "2") (pinfunction "2_2") (pintype "passive"))
      (node (ref "C232") (pin "1") (pinfunction "1_1") (pintype "passive"))
      (node (ref "R200") (pin "2") (pinfunction "2_2") (pintype "passive"))
      (node (ref "R204") (pin "2") (pinfunction "2_2") (pintype "passive"))
      (node (ref "R205") (pin "1") (pinfunction "1_1") (pintype "passive"))
      (node (ref "U200") (pin "C1") (pinfunction "VDDIN_C1") (pintype "power_in"))
      (node (ref "U200") (pin "D1") (pinfunction "ADVREFP_D1") (pintype "passive"))
      (node (ref "U200") (pin "E7") (pinfunction "VDDUTMII_E7") (pintype "power_in"))
      (node (ref "U200") (pin "G8") (pinfunction "VDDIO_G8") (pintype "power_in"))
      (node (ref "U200") (pin "H6") (pinfunction "VDDIO_H6") (pintype "power_in"))
      (node (ref "U200") (pin "H7") (pinfunction "VDDIO_H7") (pintype "power_in"))
      (node (ref "U201") (pin "A7") (pinfunction "VDDQ_A7") (pintype "power_in"))
      (node (ref "U201") (pin "A9") (pinfunction "VDD_A9") (pintype "power_in"))
      (node (ref "U201") (pin "B3") (pinfunction "VDDQ_B3") (pintype "power_in"))
      (node (ref "U201") (pin "C7") (pinfunction "VDDQ_C7") (pintype "power_in"))
      (node (ref "U201") (pin "D3") (pinfunction "VDDQ_D3") (pintype "power_in"))
      (node (ref "U201") (pin "E7") (pinfunction "VDD_E7") (pintype "power_in"))
      (node (ref "U201") (pin "J9") (pinfunction "VDD_J9") (pintype "power_in"))
      (node (ref "U202") (pin "4") (pinfunction "VDD_4") (pintype "power_in"))
    )
    (net (code "82") (name "VDDCORE") (class "Default")
      (node (ref "C205") (pin "1") (pinfunction "1_1") (pintype "passive"))
      (node (ref "C206") (pin "2") (pinfunction "2_2") (pintype "passive"))
      (node (ref "C207") (pin "2") (pinfunction "2_2") (pintype "passive"))
      (node (ref "C213") (pin "2") (pinfunction "2_2") (pintype "passive"))
      (node (ref "C214") (pin "1") (pinfunction "1_1") (pintype "passive"))
      (node (ref "C228") (pin "2") (pinfunction "2_2") (pintype "passive"))
      (node (ref "C229") (pin "2") (pinfunction "2_2") (pintype "passive"))
      (node (ref "FB200") (pin "1") (pinfunction "1_1") (pintype "passive"))
      (node (ref "FB201") (pin "1") (pinfunction "1_1") (pintype "passive"))
      (node (ref "TP204") (pin "1") (pintype "passive"))
      (node (ref "U200") (pin "C3") (pinfunction "VDDOUT_C3") (pintype "power_in"))
      (node (ref "U200") (pin "E8") (pinfunction "VDDCORE_E8") (pintype "power_in"))
      (node (ref "U200") (pin "H5") (pinfunction "VDDCORE_H5") (pintype "power_in"))
      (node (ref "U200") (pin "H8") (pinfunction "VDDCORE_H8") (pintype "power_in"))
    )
    (net (code "83") (name "VDDPLL") (class "Default")
      (node (ref "C203") (pin "2") (pinfunction "2_2") (pintype "passive"))
      (node (ref "C233") (pin "2") (pinfunction "2_2") (pintype "passive"))
      (node (ref "FB200") (pin "2") (pinfunction "2_2") (pintype "passive"))
      (node (ref "TP200") (pin "1") (pintype "passive"))
      (node (ref "U200") (pin "J7") (pinfunction "VDDPLL_J7") (pintype "power_in"))
    )
    (net (code "84") (name "VDDUTMIC") (class "Default")
      (node (ref "C204") (pin "2") (pinfunction "2_2") (pintype "passive"))
      (node (ref "C234") (pin "2") (pinfunction "2_2") (pintype "passive"))
      (node (ref "FB201") (pin "2") (pinfunction "2_2") (pintype "passive"))
      (node (ref "TP201") (pin "1") (pintype "passive"))
      (node (ref "U200") (pin "B3") (pinfunction "VDDUTMIC_B3") (pintype "power_in"))
    )
    (net (code "85") (name "unconnected-(U200A-JTAGSEL-PadB11)") (class "Default")
      (node (ref "U200") (pin "B11") (pinfunction "JTAGSEL_B11") (pintype "input+no_connect"))
    )
    (net (code "86") (name "unconnected-(U200A-PB3-PadJ3)") (class "Default")
      (node (ref "U200") (pin "J3") (pinfunction "PB3_J3") (pintype "bidirectional+no_connect"))
    )
    (net (code "87") (name "unconnected-(U200A-PB8{slash}XOUT-PadA3)") (class "Default")
      (node (ref "U200") (pin "A3") (pinfunction "PB8/XOUT_A3") (pintype "bidirectional+no_connect"))
    )
    (net (code "88") (name "unconnected-(U200A-TST-PadH11)") (class "Default")
      (node (ref "U200") (pin "H11") (pinfunction "TST_H11") (pintype "input+no_connect"))
    )
    (net (code "89") (name "unconnected-(U200B-PA1-PadD12)") (class "Default")
      (node (ref "U200") (pin "D12") (pinfunction "PA1_D12") (pintype "bidirectional+no_connect"))
    )
    (net (code "90") (name "unconnected-(U200B-PA6-PadB9)") (class "Default")
      (node (ref "U200") (pin "B9") (pinfunction "PA6_B9") (pintype "bidirectional+no_connect"))
    )
    (net (code "91") (name "unconnected-(U200B-PA9-PadM12)") (class "Default")
      (node (ref "U200") (pin "M12") (pinfunction "PA9_M12") (pintype "bidirectional+no_connect"))
    )
    (net (code "92") (name "unconnected-(U200B-PA10-PadL9)") (class "Default")
      (node (ref "U200") (pin "L9") (pinfunction "PA10_L9") (pintype "bidirectional+no_connect"))
    )
    (net (code "93") (name "unconnected-(U200B-PA18-PadH2)") (class "Default")
      (node (ref "U200") (pin "H2") (pinfunction "PA18_H2") (pintype "bidirectional+no_connect"))
    )
    (net (code "94") (name "unconnected-(U200B-PA19-PadH1)") (class "Default")
      (node (ref "U200") (pin "H1") (pinfunction "PA19_H1") (pintype "bidirectional+no_connect"))
    )
    (net (code "95") (name "unconnected-(U200B-PA21-PadK2)") (class "Default")
      (node (ref "U200") (pin "K2") (pinfunction "PA21_K2") (pintype "bidirectional+no_connect"))
    )
    (net (code "96") (name "unconnected-(U200B-PA22-PadK3)") (class "Default")
      (node (ref "U200") (pin "K3") (pinfunction "PA22_K3") (pintype "bidirectional+no_connect"))
    )
    (net (code "97") (name "unconnected-(U200B-PA23-PadL4)") (class "Default")
      (node (ref "U200") (pin "L4") (pinfunction "PA23_L4") (pintype "bidirectional+no_connect"))
    )
    (net (code "98") (name "unconnected-(U200B-PA24-PadL7)") (class "Default")
      (node (ref "U200") (pin "L7") (pinfunction "PA24_L7") (pintype "bidirectional+no_connect"))
    )
    (net (code "99") (name "unconnected-(U200B-PA29-PadA6)") (class "Default")
      (node (ref "U200") (pin "A6") (pinfunction "PA29_A6") (pintype "bidirectional+no_connect"))
    )
    (net (code "100") (name "unconnected-(U200C-PC8-PadJ12)") (class "Default")
      (node (ref "U200") (pin "J12") (pinfunction "PC8_J12") (pintype "bidirectional+no_connect"))
    )
    (net (code "101") (name "unconnected-(U200C-PC9-PadG11)") (class "Default")
      (node (ref "U200") (pin "G11") (pinfunction "PC9_G11") (pintype "bidirectional+no_connect"))
    )
    (net (code "102") (name "unconnected-(U200C-PC10-PadF10)") (class "Default")
      (node (ref "U200") (pin "F10") (pinfunction "PC10_F10") (pintype "bidirectional+no_connect"))
    )
    (net (code "103") (name "unconnected-(U200C-PC11-PadF11)") (class "Default")
      (node (ref "U200") (pin "F11") (pinfunction "PC11_F11") (pintype "bidirectional+no_connect"))
    )
    (net (code "104") (name "unconnected-(U200C-PC12-PadF4)") (class "Default")
      (node (ref "U200") (pin "F4") (pinfunction "PC12_F4") (pintype "bidirectional+no_connect"))
    )
    (net (code "105") (name "unconnected-(U200C-PC13-PadG2)") (class "Default")
      (node (ref "U200") (pin "G2") (pinfunction "PC13_G2") (pintype "bidirectional+no_connect"))
    )
    (net (code "106") (name "unconnected-(U200C-PC14-PadE10)") (class "Default")
      (node (ref "U200") (pin "E10") (pinfunction "PC14_E10") (pintype "bidirectional+no_connect"))
    )
    (net (code "107") (name "unconnected-(U200C-PC15-PadG1)") (class "Default")
      (node (ref "U200") (pin "G1") (pinfunction "PC15_G1") (pintype "bidirectional+no_connect"))
    )
    (net (code "108") (name "unconnected-(U200C-PC16-PadD11)") (class "Default")
      (node (ref "U200") (pin "D11") (pinfunction "PC16_D11") (pintype "bidirectional+no_connect"))
    )
    (net (code "109") (name "unconnected-(U200C-PC17-PadB12)") (class "Default")
      (node (ref "U200") (pin "B12") (pinfunction "PC17_B12") (pintype "bidirectional+no_connect"))
    )
    (net (code "110") (name "unconnected-(U200C-PC19-PadD8)") (class "Default")
      (node (ref "U200") (pin "D8") (pinfunction "PC19_D8") (pintype "bidirectional+no_connect"))
    )
    (net (code "111") (name "unconnected-(U200C-PC30-PadF1)") (class "Default")
      (node (ref "U200") (pin "F1") (pinfunction "PC30_F1") (pintype "bidirectional+no_connect"))
    )
    (net (code "112") (name "unconnected-(U200D-PD2-PadA5)") (class "Default")
      (node (ref "U200") (pin "A5") (pinfunction "PD2_A5") (pintype "bidirectional+no_connect"))
    )
    (net (code "113") (name "unconnected-(U200D-PD3-PadB7)") (class "Default")
      (node (ref "U200") (pin "B7") (pinfunction "PD3_B7") (pintype "bidirectional+no_connect"))
    )
    (net (code "114") (name "unconnected-(U200D-PD4-PadD6)") (class "Default")
      (node (ref "U200") (pin "D6") (pinfunction "PD4_D6") (pintype "bidirectional+no_connect"))
    )
    (net (code "115") (name "unconnected-(U200D-PD5-PadD7)") (class "Default")
      (node (ref "U200") (pin "D7") (pinfunction "PD5_D7") (pintype "bidirectional+no_connect"))
    )
    (net (code "116") (name "unconnected-(U200D-PD6-PadA8)") (class "Default")
      (node (ref "U200") (pin "A8") (pinfunction "PD6_A8") (pintype "bidirectional+no_connect"))
    )
    (net (code "117") (name "unconnected-(U200D-PD7-PadB8)") (class "Default")
      (node (ref "U200") (pin "B8") (pinfunction "PD7_B8") (pintype "bidirectional+no_connect"))
    )
    (net (code "118") (name "unconnected-(U200D-PD8-PadE9)") (class "Default")
      (node (ref "U200") (pin "E9") (pinfunction "PD8_E9") (pintype "bidirectional+no_connect"))
    )
    (net (code "119") (name "unconnected-(U200D-PD9-PadD9)") (class "Default")
      (node (ref "U200") (pin "D9") (pinfunction "PD9_D9") (pintype "bidirectional+no_connect"))
    )
    (net (code "120") (name "unconnected-(U200D-PD12-PadG10)") (class "Default")
      (node (ref "U200") (pin "G10") (pinfunction "PD12_G10") (pintype "bidirectional+no_connect"))
    )
    (net (code "121") (name "unconnected-(U200D-PD19-PadM9)") (class "Default")
      (node (ref "U200") (pin "M9") (pinfunction "PD19_M9") (pintype "bidirectional+no_connect"))
    )
    (net (code "122") (name "unconnected-(U200D-PD20-PadK9)") (class "Default")
      (node (ref "U200") (pin "K9") (pinfunction "PD20_K9") (pintype "bidirectional+no_connect"))
    )
    (net (code "123") (name "unconnected-(U200D-PD21-PadH9)") (class "Default")
      (node (ref "U200") (pin "H9") (pinfunction "PD21_H9") (pintype "bidirectional+no_connect"))
    )
    (net (code "124") (name "unconnected-(U200D-PD22-PadM8)") (class "Default")
      (node (ref "U200") (pin "M8") (pinfunction "PD22_M8") (pintype "bidirectional+no_connect"))
    )
    (net (code "125") (name "unconnected-(U200D-PD27-PadJ6)") (class "Default")
      (node (ref "U200") (pin "J6") (pinfunction "PD27_J6") (pintype "bidirectional+no_connect"))
    )
    (net (code "126") (name "unconnected-(U200D-PD28-PadK10)") (class "Default")
      (node (ref "U200") (pin "K10") (pinfunction "PD28_K10") (pintype "bidirectional+no_connect"))
    )
    (net (code "127") (name "unconnected-(U200D-PD30-PadM1)") (class "Default")
      (node (ref "U200") (pin "M1") (pinfunction "PD30_M1") (pintype "bidirectional+no_connect"))
    )
    (net (code "128") (name "unconnected-(U201-NC-PadE2)") (class "Default")
      (node (ref "U201") (pin "E2") (pinfunction "NC_E2") (pintype "passive+no_connect"))
    )
    (net (code "129") (name "unconnected-(U201-NC-PadG1)") (class "Default")
      (node (ref "U201") (pin "G1") (pinfunction "NC_G1") (pintype "passive+no_connect"))
    )
    (net (code "130") (name "unconnected-(U202-OE-Pad1)") (class "Default")
      (node (ref "U202") (pin "1") (pinfunction "OE_1") (pintype "input+no_connect"))
    )
  )
)
